# MAIN_SCHE.net
KiCad netlist of a schematic drawn in Altium Designer
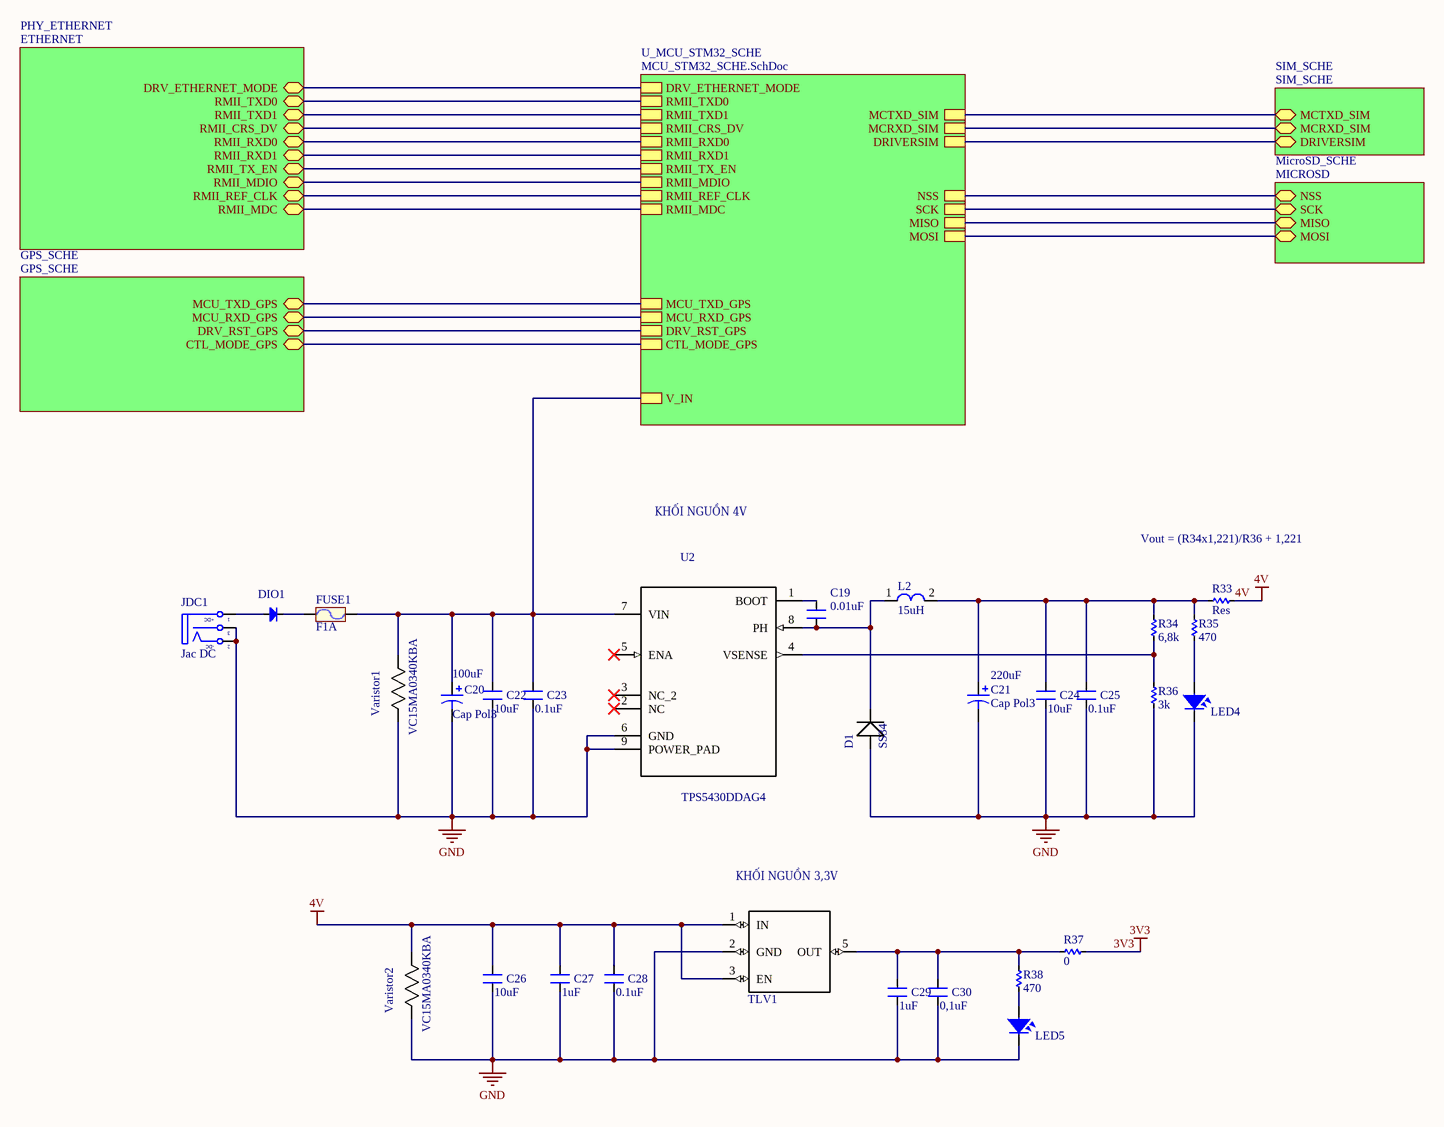
[diagram p0: MAIN_SCHE.SchDoc]

(export (version "E")
  (design (tool "Eeschema 10.0.6"))
  (components
    (comp (ref "C19")
      (value "0.01uF")
      (footprint "res 0805 - duplicate")
      (description "Cap SMD")
      (libsource (lib "PART") (part "CM"))
    )
    (comp (ref "C20")
      (value "Cap Pol3")
      (footprint "cap_100uf")
      (description "Polarized Capacitor (Surface Mount)")
      (fields (field (name "ALTIUM_VALUE") "100uF") (field (name "PUBLISHER") "Altium Limited"))
      (libsource (lib "Miscellaneous Devices") (part "Cap Pol3"))
    )
    (comp (ref "C21")
      (value "Cap Pol3")
      (footprint "Cap_tant_220uF")
      (description "Polarized Capacitor (Surface Mount)")
      (fields (field (name "ALTIUM_VALUE") "220uF") (field (name "PUBLISHER") "Altium Limited"))
      (libsource (lib "Miscellaneous Devices") (part "Cap Pol3"))
    )
    (comp (ref "C22")
      (value "10uF")
      (footprint "res 0805 - duplicate")
      (description "Cap SMD")
      (libsource (lib "PART") (part "CM"))
    )
    (comp (ref "C23")
      (value "0.1uF")
      (footprint "res 0805 - duplicate")
      (description "Cap SMD")
      (libsource (lib "PART") (part "CM"))
    )
    (comp (ref "C24")
      (value "10uF")
      (footprint "res 0805 - duplicate")
      (description "Cap SMD")
      (libsource (lib "PART") (part "CM"))
    )
    (comp (ref "C25")
      (value "0.1uF")
      (footprint "res 0805 - duplicate")
      (description "Cap SMD")
      (libsource (lib "PART") (part "CM"))
    )
    (comp (ref "C26")
      (value "10uF")
      (footprint "res 0805 - duplicate")
      (description "Cap SMD")
      (libsource (lib "PART") (part "CM"))
    )
    (comp (ref "C27")
      (value "1uF")
      (footprint "res 0805 - duplicate")
      (description "Cap SMD")
      (libsource (lib "PART") (part "CM"))
    )
    (comp (ref "C28")
      (value "0.1uF")
      (footprint "res 0805 - duplicate")
      (description "Cap SMD")
      (libsource (lib "PART") (part "CM"))
    )
    (comp (ref "C29")
      (value "1uF")
      (footprint "res 0805 - duplicate")
      (description "Cap SMD")
      (libsource (lib "PART") (part "CM"))
    )
    (comp (ref "C30")
      (value "0,1uF")
      (footprint "res 0805 - duplicate")
      (description "Cap SMD")
      (libsource (lib "PART") (part "CM"))
    )
    (comp (ref "D1")
      (value "SS34")
      (footprint "SS34")
      (description "Rectifier, Schottky; DO-214AB; 3.0A IF; 0.75V; 40V; 100A IFRM; 10000V/us; 1000pF")
      (fields (field (name "DIGI-KEY_PART_NUMBER") "SS34-E3/57TGICT-ND") (field (name "MF") "Vishay"))
      (libsource (lib "SMD-DIODE-SCHOTTKY-40V-3A_DO-214AB_") (part "SMD-DIODE-SCHOTTKY-40V-3A(DO-214AB)"))
    )
    (comp (ref "DIO1")
      (value "Diode SMD")
      (footprint "DIOT-SS24")
      (description "Default Diode")
      (fields (field (name "PUBLISHER") "Altium Limited"))
      (libsource (lib "LIBRARYabc") (part "Diode SMD"))
    )
    (comp (ref "FUSE1")
      (value "F1A")
      (footprint "fuse")
      (description "Fuse")
      (fields (field (name "DESIGNED BY") "VanDungEvn"))
      (libsource (lib "syhaunguyen") (part "Fuse"))
    )
    (comp (ref "JDC1")
      (value "Jac DC")
      (footprint "DC-IN")
      (description "Jac DC input")
      (libsource (lib "syhaunguyen") (part "DCIN"))
    )
    (comp (ref "L2")
      (value "15uH")
      (footprint "L-15uH")
      (fields
        (field (name "PARTNO") "78477010")
        (field (name "MANUFACTURER") "Wurth Elektronik")
        (field (name "CREATED BY") "Baojun Chen")
      )
      (libsource (lib "LIBRARYabc") (part "L-SMD-1"))
    )
    (comp (ref "LED4")
      (value "LED")
      (footprint "res 0805 - duplicate")
      (libsource (lib "LIBRARYabc") (part "LED SMD"))
    )
    (comp (ref "LED5")
      (value "LED")
      (footprint "res 0805 - duplicate")
      (libsource (lib "LIBRARYabc") (part "LED SMD"))
    )
    (comp (ref "R33")
      (value "Res")
      (footprint "res 0805 - duplicate")
      (description "Resistor")
      (fields
        (field (name "MANUFACTURER") "Generic Components")
        (field (name "PUBLISHER") "Altium Hobart Technology Centre")
      )
      (libsource (lib "LIBRARYabc") (part "Res-SMD"))
    )
    (comp (ref "R34")
      (value "6,8k")
      (footprint "res 0805 - duplicate")
      (description "Resistor")
      (fields
        (field (name "MANUFACTURER") "Generic Components")
        (field (name "PUBLISHER") "Altium Hobart Technology Centre")
      )
      (libsource (lib "LIBRARYabc") (part "Res-SMD"))
    )
    (comp (ref "R35")
      (value "470")
      (footprint "res 0805 - duplicate")
      (description "Resistor")
      (fields
        (field (name "MANUFACTURER") "Generic Components")
        (field (name "PUBLISHER") "Altium Hobart Technology Centre")
      )
      (libsource (lib "LIBRARYabc") (part "Res-SMD"))
    )
    (comp (ref "R36")
      (value "3k")
      (footprint "res 0805 - duplicate")
      (description "Resistor")
      (fields
        (field (name "MANUFACTURER") "Generic Components")
        (field (name "PUBLISHER") "Altium Hobart Technology Centre")
      )
      (libsource (lib "LIBRARYabc") (part "Res-SMD"))
    )
    (comp (ref "R37")
      (value "0")
      (footprint "res 0805 - duplicate")
      (description "Resistor")
      (fields
        (field (name "MANUFACTURER") "Generic Components")
        (field (name "PUBLISHER") "Altium Hobart Technology Centre")
      )
      (libsource (lib "LIBRARYabc") (part "Res-SMD"))
    )
    (comp (ref "R38")
      (value "470")
      (footprint "res 0805 - duplicate")
      (description "Resistor")
      (fields
        (field (name "MANUFACTURER") "Generic Components")
        (field (name "PUBLISHER") "Altium Hobart Technology Centre")
      )
      (libsource (lib "LIBRARYabc") (part "Res-SMD"))
    )
    (comp (ref "TLV1")
      (value "TLV70233DBVR")
      (footprint "SOT23-5")
      (description "LDO voltage regulator [Texas Instruments] TLV70233DBVR LDO voltage regulator")
      (fields (field (name "MF") "Texas Instruments"))
      (libsource (lib "TLV70233DBVR") (part "TLV70233DBVR"))
    )
    (comp (ref "U2")
      (value "TPS5430DDAG4")
      (footprint "SOIC127P600X170-9N")
      (description "5.5V to 36V Input, 3A, 500kHz Step-Down Converter 8-SO PowerPAD -40 to 125")
      (fields (field (name "MF") "Texas Instruments"))
      (libsource (lib "TPS5430DDAG4") (part "TPS5430DDAG4"))
    )
    (comp (ref "Varistor1")
      (value "VC15MA0340KBA")
      (footprint "varistor")
      (description "2220 34 VDC 4000 pF Surface Mount Multilayer Ceramic Varistor")
      (fields (field (name "MF") "AVX"))
      (libsource (lib "VC15MA0340KBA") (part "VC15MA0340KBA"))
    )
    (comp (ref "Varistor2")
      (value "VC15MA0340KBA")
      (footprint "varistor")
      (description "2220 34 VDC 4000 pF Surface Mount Multilayer Ceramic Varistor")
      (fields (field (name "MF") "AVX"))
      (libsource (lib "VC15MA0340KBA") (part "VC15MA0340KBA"))
    )
  )
  (nets
    (net (code "22") (name "/V_IN") (class "Default")
      (node (ref "C20") (pin "1") (pinfunction "1_1") (pintype "passive"))
      (node (ref "C22") (pin "2") (pinfunction "2_2") (pintype "passive"))
      (node (ref "C23") (pin "2") (pinfunction "2_2") (pintype "passive"))
      (node (ref "FUSE1") (pin "2") (pinfunction "2_2") (pintype "passive"))
      (node (ref "U2") (pin "7") (pinfunction "VIN_7") (pintype "power_in"))
      (node (ref "Varistor1") (pin "1") (pinfunction "R1_1") (pintype "passive"))
    )
    (net (code "23") (name "3V3") (class "Default")
      (node (ref "R37") (pin "1") (pinfunction "1_1") (pintype "passive"))
    )
    (net (code "24") (name "4V") (class "Default")
      (node (ref "C26") (pin "2") (pinfunction "2_2") (pintype "passive"))
      (node (ref "C27") (pin "2") (pinfunction "2_2") (pintype "passive"))
      (node (ref "C28") (pin "2") (pinfunction "2_2") (pintype "passive"))
      (node (ref "R33") (pin "1") (pinfunction "1_1") (pintype "passive"))
      (node (ref "TLV1") (pin "1") (pinfunction "IN_1") (pintype "bidirectional"))
      (node (ref "TLV1") (pin "3") (pinfunction "EN_3") (pintype "bidirectional"))
      (node (ref "Varistor2") (pin "1") (pinfunction "R1_1") (pintype "passive"))
    )
    (net (code "25") (name "GND") (class "Default")
      (node (ref "C20") (pin "2") (pinfunction "2_2") (pintype "passive"))
      (node (ref "C21") (pin "2") (pinfunction "2_2") (pintype "passive"))
      (node (ref "C22") (pin "1") (pinfunction "1_1") (pintype "passive"))
      (node (ref "C23") (pin "1") (pinfunction "1_1") (pintype "passive"))
      (node (ref "C24") (pin "1") (pinfunction "1_1") (pintype "passive"))
      (node (ref "C25") (pin "1") (pinfunction "1_1") (pintype "passive"))
      (node (ref "C26") (pin "1") (pinfunction "1_1") (pintype "passive"))
      (node (ref "C27") (pin "1") (pinfunction "1_1") (pintype "passive"))
      (node (ref "C28") (pin "1") (pinfunction "1_1") (pintype "passive"))
      (node (ref "C29") (pin "1") (pinfunction "1_1") (pintype "passive"))
      (node (ref "C30") (pin "1") (pinfunction "1_1") (pintype "passive"))
      (node (ref "D1") (pin "1") (pinfunction "POS_1") (pintype "passive"))
      (node (ref "JDC1") (pin "2") (pinfunction "TN_2") (pintype "passive"))
      (node (ref "JDC1") (pin "3") (pinfunction "S_3") (pintype "power_in"))
      (node (ref "LED4") (pin "2") (pinfunction "2_2") (pintype "passive"))
      (node (ref "LED5") (pin "2") (pinfunction "2_2") (pintype "passive"))
      (node (ref "R36") (pin "2") (pinfunction "2_2") (pintype "passive"))
      (node (ref "TLV1") (pin "2") (pinfunction "GND_2") (pintype "bidirectional"))
      (node (ref "U2") (pin "6") (pinfunction "GND_6") (pintype "passive"))
      (node (ref "U2") (pin "9") (pinfunction "POWER_PAD_9") (pintype "passive"))
      (node (ref "Varistor1") (pin "2") (pinfunction "R2_2") (pintype "passive"))
      (node (ref "Varistor2") (pin "2") (pinfunction "R2_2") (pintype "passive"))
    )
    (net (code "26") (name "Net-(C21-Pad1)") (class "Default")
      (node (ref "C21") (pin "1") (pinfunction "1_1") (pintype "passive"))
      (node (ref "C24") (pin "2") (pinfunction "2_2") (pintype "passive"))
      (node (ref "C25") (pin "2") (pinfunction "2_2") (pintype "passive"))
      (node (ref "L2") (pin "2") (pinfunction "2_2") (pintype "passive"))
      (node (ref "R33") (pin "2") (pinfunction "2_2") (pintype "passive"))
      (node (ref "R34") (pin "1") (pinfunction "1_1") (pintype "passive"))
      (node (ref "R35") (pin "1") (pinfunction "1_1") (pintype "passive"))
    )
    (net (code "27") (name "Net-(D1-NEG)") (class "Default")
      (node (ref "C19") (pin "1") (pinfunction "1_1") (pintype "passive"))
      (node (ref "D1") (pin "2") (pinfunction "NEG_2") (pintype "passive"))
      (node (ref "L2") (pin "1") (pinfunction "1_1") (pintype "passive"))
      (node (ref "U2") (pin "8") (pinfunction "PH_8") (pintype "input"))
    )
    (net (code "28") (name "Net-(DIO1-A)") (class "Default")
      (node (ref "DIO1") (pin "1") (pinfunction "A_1") (pintype "passive"))
      (node (ref "JDC1") (pin "1") (pinfunction "T_1") (pintype "passive"))
    )
    (net (code "29") (name "Net-(DIO1-K)") (class "Default")
      (node (ref "DIO1") (pin "2") (pinfunction "K_2") (pintype "passive"))
      (node (ref "FUSE1") (pin "1") (pinfunction "1_1") (pintype "passive"))
    )
    (net (code "30") (name "Net-(LED4-Pad1)") (class "Default")
      (node (ref "LED4") (pin "1") (pinfunction "1_1") (pintype "passive"))
      (node (ref "R35") (pin "2") (pinfunction "2_2") (pintype "passive"))
    )
    (net (code "31") (name "Net-(LED5-Pad1)") (class "Default")
      (node (ref "LED5") (pin "1") (pinfunction "1_1") (pintype "passive"))
      (node (ref "R38") (pin "1") (pinfunction "1_1") (pintype "passive"))
    )
    (net (code "32") (name "Net-(TLV1-OUT)") (class "Default")
      (node (ref "C29") (pin "2") (pinfunction "2_2") (pintype "passive"))
      (node (ref "C30") (pin "2") (pinfunction "2_2") (pintype "passive"))
      (node (ref "R37") (pin "2") (pinfunction "2_2") (pintype "passive"))
      (node (ref "R38") (pin "2") (pinfunction "2_2") (pintype "passive"))
      (node (ref "TLV1") (pin "5") (pinfunction "OUT_5") (pintype "bidirectional"))
    )
    (net (code "33") (name "Net-(U2-BOOT)") (class "Default")
      (node (ref "C19") (pin "2") (pinfunction "2_2") (pintype "passive"))
      (node (ref "U2") (pin "1") (pinfunction "BOOT_1") (pintype "passive"))
    )
    (net (code "34") (name "Net-(U2-VSENSE)") (class "Default")
      (node (ref "R34") (pin "2") (pinfunction "2_2") (pintype "passive"))
      (node (ref "R36") (pin "1") (pinfunction "1_1") (pintype "passive"))
      (node (ref "U2") (pin "4") (pinfunction "VSENSE_4") (pintype "output"))
    )
    (net (code "35") (name "unconnected-(U2-ENA-Pad5)") (class "Default")
      (node (ref "U2") (pin "5") (pinfunction "ENA_5") (pintype "input+no_connect"))
    )
    (net (code "36") (name "unconnected-(U2-NC-Pad2)") (class "Default")
      (node (ref "U2") (pin "2") (pinfunction "NC_2") (pintype "passive+no_connect"))
    )
    (net (code "37") (name "unconnected-(U2-NC_2-Pad3)") (class "Default")
      (node (ref "U2") (pin "3") (pinfunction "NC_2_3") (pintype "passive+no_connect"))
    )
  )
)
